# Etage_sortie_VCF.net
KiCad netlist of a schematic drawn in EAGLE
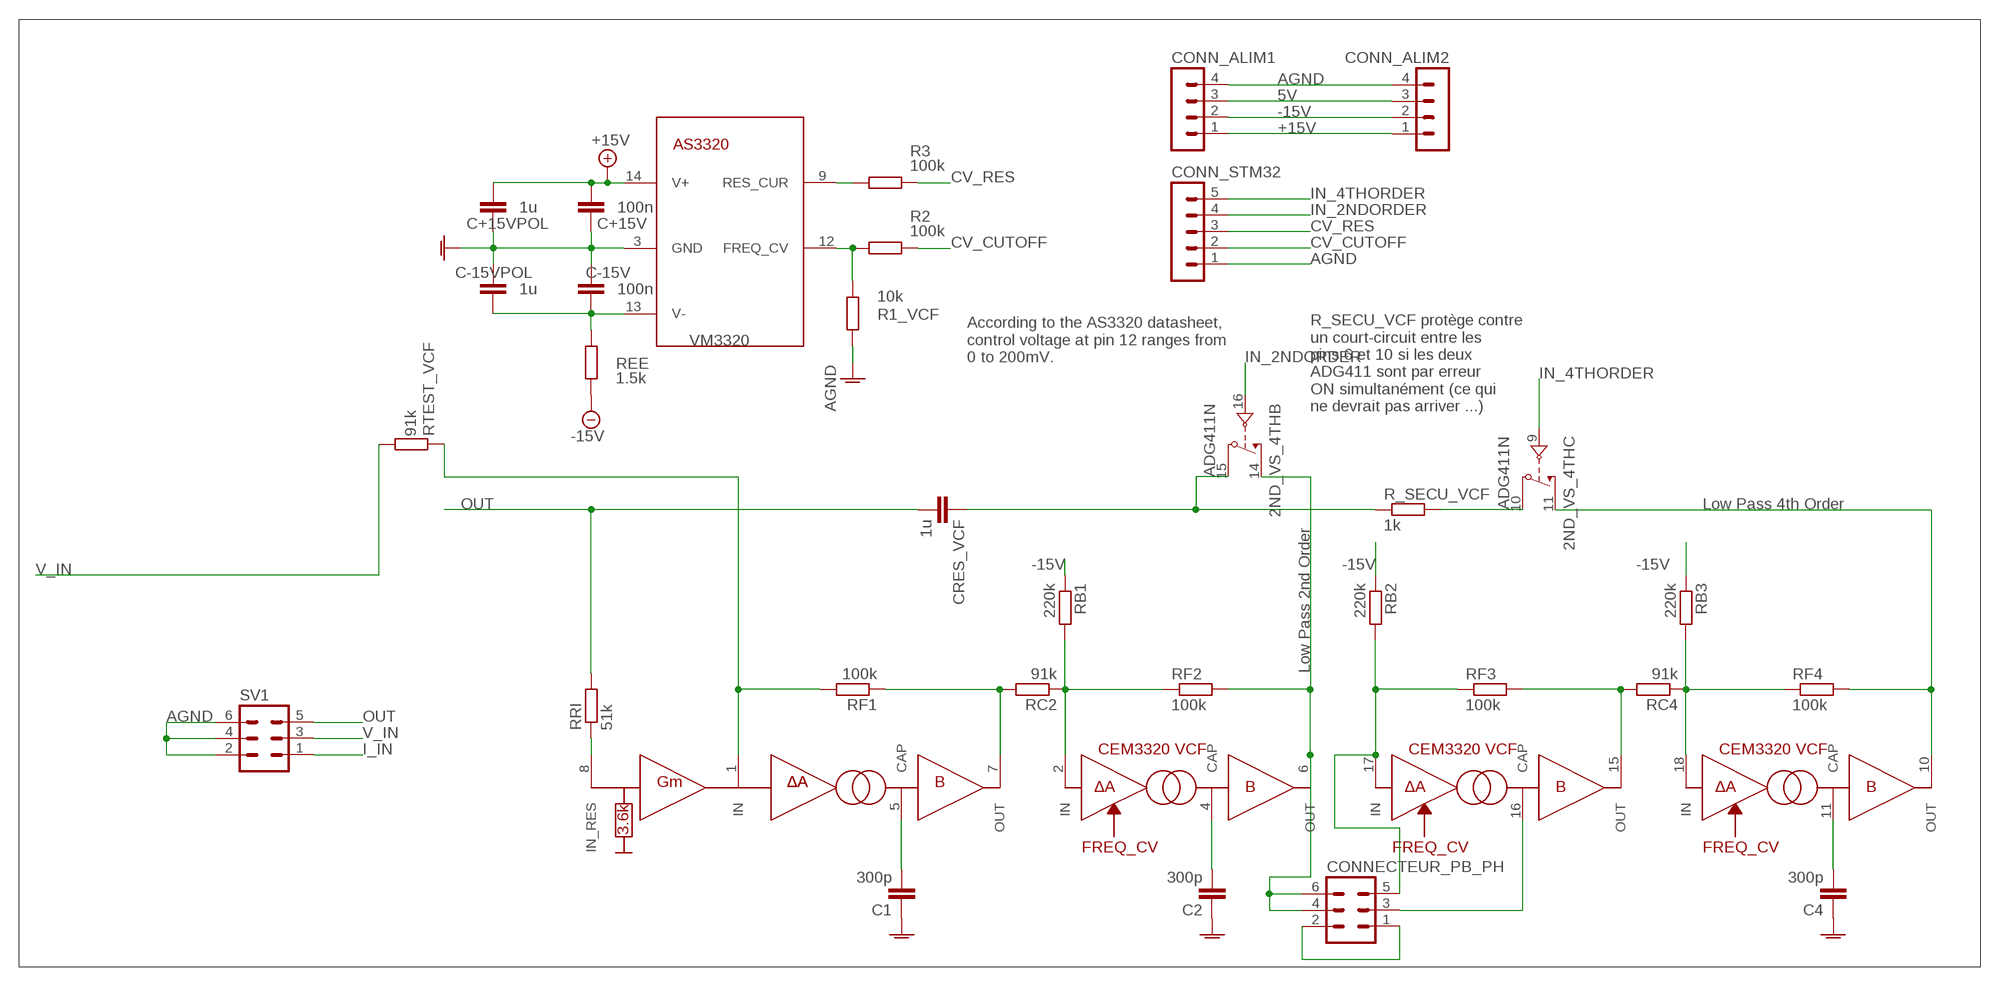
[diagram p0: schematic, sheet 1]

(export (version "E")
  (design (tool "Eeschema 10.0.6"))
  (components
    (comp (ref "2ND_VS_4TH")
      (value "ADG411N")
      (footprint "eagle-import:DIL16")
      (fields (field (name "MF") "ALTERA CORPORATION") (field (name "MPN") "ADG411BN"))
      (libsource (lib "eagle-import") (part "ADG411N"))
    )
    (comp (ref "C+15V")
      (value "100n")
      (footprint "eagle-import:C075-032X103")
      (libsource (lib "eagle-import") (part "C-EU075-032X103"))
    )
    (comp (ref "C+15VPOL")
      (value "1u")
      (footprint "eagle-import:C075-032X103")
      (libsource (lib "eagle-import") (part "C-EU075-032X103"))
    )
    (comp (ref "C-15V")
      (value "100n")
      (footprint "eagle-import:C075-032X103")
      (libsource (lib "eagle-import") (part "C-EU075-032X103"))
    )
    (comp (ref "C-15VPOL")
      (value "1u")
      (footprint "eagle-import:C075-032X103")
      (libsource (lib "eagle-import") (part "C-EU075-032X103"))
    )
    (comp (ref "C1")
      (value "300p")
      (footprint "eagle-import:C075-032X103")
      (libsource (lib "eagle-import") (part "C-EU075-032X103"))
    )
    (comp (ref "C2")
      (value "300p")
      (footprint "eagle-import:C075-032X103")
      (libsource (lib "eagle-import") (part "C-EU075-032X103"))
    )
    (comp (ref "C4")
      (value "300p")
      (footprint "eagle-import:C075-032X103")
      (libsource (lib "eagle-import") (part "C-EU075-032X103"))
    )
    (comp (ref "CONNECTEUR_PB_PH")
      (value "MA03-2")
      (footprint "eagle-import:MA03-2")
      (libsource (lib "eagle-import") (part "MA03-2"))
    )
    (comp (ref "CONN_ALIM1")
      (value "MA04-1")
      (footprint "eagle-import:MA04-1")
      (libsource (lib "eagle-import") (part "MA04-1"))
    )
    (comp (ref "CONN_ALIM2")
      (value "MA04-1")
      (footprint "eagle-import:MA04-1")
      (libsource (lib "eagle-import") (part "MA04-1"))
    )
    (comp (ref "CONN_STM32")
      (value "MA05-1")
      (footprint "eagle-import:MA05-1")
      (libsource (lib "eagle-import") (part "MA05-1"))
    )
    (comp (ref "CRES_VCF")
      (value "1u")
      (footprint "eagle-import:C075-032X103")
      (libsource (lib "eagle-import") (part "C-EU075-032X103"))
    )
    (comp (ref "R1_VCF")
      (value "10k")
      (footprint "eagle-import:0204_7")
      (libsource (lib "eagle-import") (part "R-EU_0204/7"))
    )
    (comp (ref "R2")
      (value "100k")
      (footprint "eagle-import:0204_7")
      (libsource (lib "eagle-import") (part "R-EU_0204/7"))
    )
    (comp (ref "R3")
      (value "100k")
      (footprint "eagle-import:0204_7")
      (libsource (lib "eagle-import") (part "R-EU_0204/7"))
    )
    (comp (ref "RB1")
      (value "220k")
      (footprint "eagle-import:0207_10")
      (libsource (lib "eagle-import") (part "R-EU_0207/10"))
    )
    (comp (ref "RB2")
      (value "220k")
      (footprint "eagle-import:0204_7")
      (libsource (lib "eagle-import") (part "R-EU_0204/7"))
    )
    (comp (ref "RB3")
      (value "220k")
      (footprint "eagle-import:0204_7")
      (libsource (lib "eagle-import") (part "R-EU_0204/7"))
    )
    (comp (ref "RC2")
      (value "91k")
      (footprint "eagle-import:0204_7")
      (libsource (lib "eagle-import") (part "R-EU_0204/7"))
    )
    (comp (ref "RC4")
      (value "91k")
      (footprint "eagle-import:0204_7")
      (libsource (lib "eagle-import") (part "R-EU_0204/7"))
    )
    (comp (ref "REE")
      (value "1.5k")
      (footprint "eagle-import:0207_10")
      (libsource (lib "eagle-import") (part "R-EU_0207/10"))
    )
    (comp (ref "RF1")
      (value "100k")
      (footprint "eagle-import:0207_10")
      (libsource (lib "eagle-import") (part "R-EU_0207/10"))
    )
    (comp (ref "RF2")
      (value "100k")
      (footprint "eagle-import:0204_7")
      (libsource (lib "eagle-import") (part "R-EU_0204/7"))
    )
    (comp (ref "RF3")
      (value "100k")
      (footprint "eagle-import:0207_10")
      (libsource (lib "eagle-import") (part "R-EU_0207/10"))
    )
    (comp (ref "RF4")
      (value "100k")
      (footprint "eagle-import:0204_7")
      (libsource (lib "eagle-import") (part "R-EU_0204/7"))
    )
    (comp (ref "RRI")
      (value "51k")
      (footprint "eagle-import:0207_10")
      (libsource (lib "eagle-import") (part "R-EU_0207/10"))
    )
    (comp (ref "RTEST_VCF")
      (value "91k")
      (footprint "eagle-import:0207_10")
      (libsource (lib "eagle-import") (part "R-EU_0207/10"))
    )
    (comp (ref "R_SECU_VCF")
      (value "1k")
      (footprint "eagle-import:0204_7")
      (libsource (lib "eagle-import") (part "R-EU_0204/7"))
    )
    (comp (ref "SV1")
      (value "MA03-2")
      (footprint "eagle-import:MA03-2")
      (libsource (lib "eagle-import") (part "MA03-2"))
    )
    (comp (ref "VCF")
      (value "AS3320")
      (footprint "eagle-import:DIL18")
      (libsource (lib "eagle-import") (part "AS3320"))
    )
  )
  (nets
    (net (code "1") (name "+15V") (class "Default")
      (node (ref "C+15V") (pin "2") (pinfunction "2_2") (pintype "passive"))
      (node (ref "C+15VPOL") (pin "2") (pinfunction "2_2") (pintype "passive"))
      (node (ref "CONN_ALIM1") (pin "1") (pinfunction "1_1") (pintype "passive"))
      (node (ref "CONN_ALIM2") (pin "1") (pinfunction "1_1") (pintype "passive"))
      (node (ref "VCF") (pin "14") (pinfunction "V+_14") (pintype "bidirectional"))
    )
    (net (code "2") (name "-15V") (class "Default")
      (node (ref "CONN_ALIM1") (pin "2") (pinfunction "2_2") (pintype "passive"))
      (node (ref "CONN_ALIM2") (pin "2") (pinfunction "2_2") (pintype "passive"))
      (node (ref "RB1") (pin "1") (pinfunction "1_1") (pintype "passive"))
      (node (ref "RB2") (pin "1") (pinfunction "1_1") (pintype "passive"))
      (node (ref "RB3") (pin "1") (pinfunction "1_1") (pintype "passive"))
      (node (ref "REE") (pin "1") (pinfunction "1_1") (pintype "passive"))
    )
    (net (code "3") (name "/5V") (class "Default")
      (node (ref "CONN_ALIM1") (pin "3") (pinfunction "3_3") (pintype "passive"))
      (node (ref "CONN_ALIM2") (pin "3") (pinfunction "3_3") (pintype "passive"))
    )
    (net (code "4") (name "/CV_CUTOFF") (class "Default")
      (node (ref "CONN_STM32") (pin "2") (pinfunction "2_2") (pintype "passive"))
      (node (ref "R2") (pin "2") (pinfunction "2_2") (pintype "passive"))
    )
    (net (code "5") (name "/CV_RES") (class "Default")
      (node (ref "CONN_STM32") (pin "3") (pinfunction "3_3") (pintype "passive"))
      (node (ref "R3") (pin "2") (pinfunction "2_2") (pintype "passive"))
    )
    (net (code "6") (name "/IN_2NDORDER") (class "Default")
      (node (ref "2ND_VS_4TH") (pin "16") (pinfunction "IN_16") (pintype "input"))
      (node (ref "CONN_STM32") (pin "4") (pinfunction "4_4") (pintype "passive"))
    )
    (net (code "7") (name "/IN_4THORDER") (class "Default")
      (node (ref "2ND_VS_4TH") (pin "9") (pinfunction "IN_9") (pintype "input"))
      (node (ref "CONN_STM32") (pin "5") (pinfunction "5_5") (pintype "passive"))
    )
    (net (code "8") (name "/I_IN") (class "Default")
      (node (ref "SV1") (pin "1") (pinfunction "1_1") (pintype "passive"))
    )
    (net (code "9") (name "/OUT") (class "Default")
      (node (ref "CRES_VCF") (pin "2") (pinfunction "2_2") (pintype "passive"))
      (node (ref "RRI") (pin "2") (pinfunction "2_2") (pintype "passive"))
      (node (ref "SV1") (pin "5") (pinfunction "5_5") (pintype "passive"))
    )
    (net (code "10") (name "/VM3320") (class "Default")
      (node (ref "C-15V") (pin "1") (pinfunction "1_1") (pintype "passive"))
      (node (ref "C-15VPOL") (pin "1") (pinfunction "1_1") (pintype "passive"))
      (node (ref "REE") (pin "2") (pinfunction "2_2") (pintype "passive"))
      (node (ref "VCF") (pin "13") (pinfunction "V-_13") (pintype "bidirectional"))
    )
    (net (code "11") (name "/V_IN") (class "Default")
      (node (ref "RTEST_VCF") (pin "1") (pinfunction "1_1") (pintype "passive"))
      (node (ref "SV1") (pin "3") (pinfunction "3_3") (pintype "passive"))
    )
    (net (code "12") (name "AGND") (class "Default")
      (node (ref "C+15V") (pin "1") (pinfunction "1_1") (pintype "passive"))
      (node (ref "C+15VPOL") (pin "1") (pinfunction "1_1") (pintype "passive"))
      (node (ref "C-15V") (pin "2") (pinfunction "2_2") (pintype "passive"))
      (node (ref "C-15VPOL") (pin "2") (pinfunction "2_2") (pintype "passive"))
      (node (ref "C1") (pin "1") (pinfunction "1_1") (pintype "passive"))
      (node (ref "C2") (pin "1") (pinfunction "1_1") (pintype "passive"))
      (node (ref "C4") (pin "1") (pinfunction "1_1") (pintype "passive"))
      (node (ref "CONN_ALIM1") (pin "4") (pinfunction "4_4") (pintype "passive"))
      (node (ref "CONN_ALIM2") (pin "4") (pinfunction "4_4") (pintype "passive"))
      (node (ref "CONN_STM32") (pin "1") (pinfunction "1_1") (pintype "passive"))
      (node (ref "R1_VCF") (pin "2") (pinfunction "2_2") (pintype "passive"))
      (node (ref "SV1") (pin "2") (pinfunction "2_2") (pintype "passive"))
      (node (ref "SV1") (pin "4") (pinfunction "4_4") (pintype "passive"))
      (node (ref "SV1") (pin "6") (pinfunction "6_6") (pintype "passive"))
      (node (ref "VCF") (pin "3") (pinfunction "GND_3") (pintype "bidirectional"))
    )
    (net (code "13") (name "Net-(2ND_VS_4THB-D)") (class "Default")
      (node (ref "2ND_VS_4TH") (pin "15") (pinfunction "D_15") (pintype "passive"))
      (node (ref "CRES_VCF") (pin "1") (pinfunction "1_1") (pintype "passive"))
      (node (ref "R_SECU_VCF") (pin "1") (pinfunction "1_1") (pintype "passive"))
    )
    (net (code "14") (name "Net-(2ND_VS_4THB-S)") (class "Default")
      (node (ref "2ND_VS_4TH") (pin "14") (pinfunction "S_14") (pintype "passive"))
      (node (ref "CONNECTEUR_PB_PH") (pin "4") (pinfunction "4_4") (pintype "passive"))
      (node (ref "CONNECTEUR_PB_PH") (pin "6") (pinfunction "6_6") (pintype "passive"))
      (node (ref "RF2") (pin "2") (pinfunction "2_2") (pintype "passive"))
      (node (ref "VCF") (pin "6") (pinfunction "OUT_6") (pintype "bidirectional"))
    )
    (net (code "15") (name "Net-(2ND_VS_4THC-D)") (class "Default")
      (node (ref "2ND_VS_4TH") (pin "10") (pinfunction "D_10") (pintype "passive"))
      (node (ref "R_SECU_VCF") (pin "2") (pinfunction "2_2") (pintype "passive"))
    )
    (net (code "16") (name "Net-(2ND_VS_4THC-S)") (class "Default")
      (node (ref "2ND_VS_4TH") (pin "11") (pinfunction "S_11") (pintype "passive"))
      (node (ref "RF4") (pin "2") (pinfunction "2_2") (pintype "passive"))
      (node (ref "VCF") (pin "10") (pinfunction "OUT_10") (pintype "bidirectional"))
    )
    (net (code "17") (name "Net-(CONNECTEUR_PB_PH-Pad1)") (class "Default")
      (node (ref "CONNECTEUR_PB_PH") (pin "1") (pinfunction "1_1") (pintype "passive"))
      (node (ref "CONNECTEUR_PB_PH") (pin "2") (pinfunction "2_2") (pintype "passive"))
    )
    (net (code "18") (name "Net-(VCFA-CAP)") (class "Default")
      (node (ref "C1") (pin "2") (pinfunction "2_2") (pintype "passive"))
      (node (ref "VCF") (pin "5") (pinfunction "CAP_5") (pintype "bidirectional"))
    )
    (net (code "19") (name "Net-(VCFA-IN)") (class "Default")
      (node (ref "RF1") (pin "2") (pinfunction "2_2") (pintype "passive"))
      (node (ref "RTEST_VCF") (pin "2") (pinfunction "2_2") (pintype "passive"))
      (node (ref "VCF") (pin "1") (pinfunction "IN_1") (pintype "bidirectional"))
    )
    (net (code "20") (name "Net-(VCFA-IN_RES)") (class "Default")
      (node (ref "RRI") (pin "1") (pinfunction "1_1") (pintype "passive"))
      (node (ref "VCF") (pin "8") (pinfunction "IN_RES_8") (pintype "bidirectional"))
    )
    (net (code "21") (name "Net-(VCFA-OUT)") (class "Default")
      (node (ref "RC2") (pin "2") (pinfunction "2_2") (pintype "passive"))
      (node (ref "RF1") (pin "1") (pinfunction "1_1") (pintype "passive"))
      (node (ref "VCF") (pin "7") (pinfunction "OUT_7") (pintype "bidirectional"))
    )
    (net (code "22") (name "Net-(VCFB-CAP)") (class "Default")
      (node (ref "C2") (pin "2") (pinfunction "2_2") (pintype "passive"))
      (node (ref "VCF") (pin "4") (pinfunction "CAP_4") (pintype "bidirectional"))
    )
    (net (code "23") (name "Net-(VCFB-IN)") (class "Default")
      (node (ref "RB1") (pin "2") (pinfunction "2_2") (pintype "passive"))
      (node (ref "RC2") (pin "1") (pinfunction "1_1") (pintype "passive"))
      (node (ref "RF2") (pin "1") (pinfunction "1_1") (pintype "passive"))
      (node (ref "VCF") (pin "2") (pinfunction "IN_2") (pintype "bidirectional"))
    )
    (net (code "24") (name "Net-(VCFC-CAP)") (class "Default")
      (node (ref "C4") (pin "2") (pinfunction "2_2") (pintype "passive"))
      (node (ref "VCF") (pin "11") (pinfunction "CAP_11") (pintype "bidirectional"))
    )
    (net (code "25") (name "Net-(VCFC-IN)") (class "Default")
      (node (ref "RB3") (pin "2") (pinfunction "2_2") (pintype "passive"))
      (node (ref "RC4") (pin "1") (pinfunction "1_1") (pintype "passive"))
      (node (ref "RF4") (pin "1") (pinfunction "1_1") (pintype "passive"))
      (node (ref "VCF") (pin "18") (pinfunction "IN_18") (pintype "bidirectional"))
    )
    (net (code "26") (name "Net-(VCFD-CAP)") (class "Default")
      (node (ref "CONNECTEUR_PB_PH") (pin "3") (pinfunction "3_3") (pintype "passive"))
      (node (ref "VCF") (pin "16") (pinfunction "CAP_16") (pintype "bidirectional"))
    )
    (net (code "27") (name "Net-(VCFD-IN)") (class "Default")
      (node (ref "CONNECTEUR_PB_PH") (pin "5") (pinfunction "5_5") (pintype "passive"))
      (node (ref "RB2") (pin "2") (pinfunction "2_2") (pintype "passive"))
      (node (ref "RF3") (pin "1") (pinfunction "1_1") (pintype "passive"))
      (node (ref "VCF") (pin "17") (pinfunction "IN_17") (pintype "bidirectional"))
    )
    (net (code "28") (name "Net-(VCFD-OUT)") (class "Default")
      (node (ref "RC4") (pin "2") (pinfunction "2_2") (pintype "passive"))
      (node (ref "RF3") (pin "2") (pinfunction "2_2") (pintype "passive"))
      (node (ref "VCF") (pin "15") (pinfunction "OUT_15") (pintype "bidirectional"))
    )
    (net (code "29") (name "Net-(VCFE-FREQ_CV)") (class "Default")
      (node (ref "R1_VCF") (pin "1") (pinfunction "1_1") (pintype "passive"))
      (node (ref "R2") (pin "1") (pinfunction "1_1") (pintype "passive"))
      (node (ref "VCF") (pin "12") (pinfunction "FREQ_CV_12") (pintype "bidirectional"))
    )
    (net (code "30") (name "Net-(VCFE-RES_CUR)") (class "Default")
      (node (ref "R3") (pin "1") (pinfunction "1_1") (pintype "passive"))
      (node (ref "VCF") (pin "9") (pinfunction "RES_CUR_9") (pintype "bidirectional"))
    )
  )
)
